# mLRS-tx-dualE28-top-v042.net
KiCad netlist of a schematic drawn in EAGLE
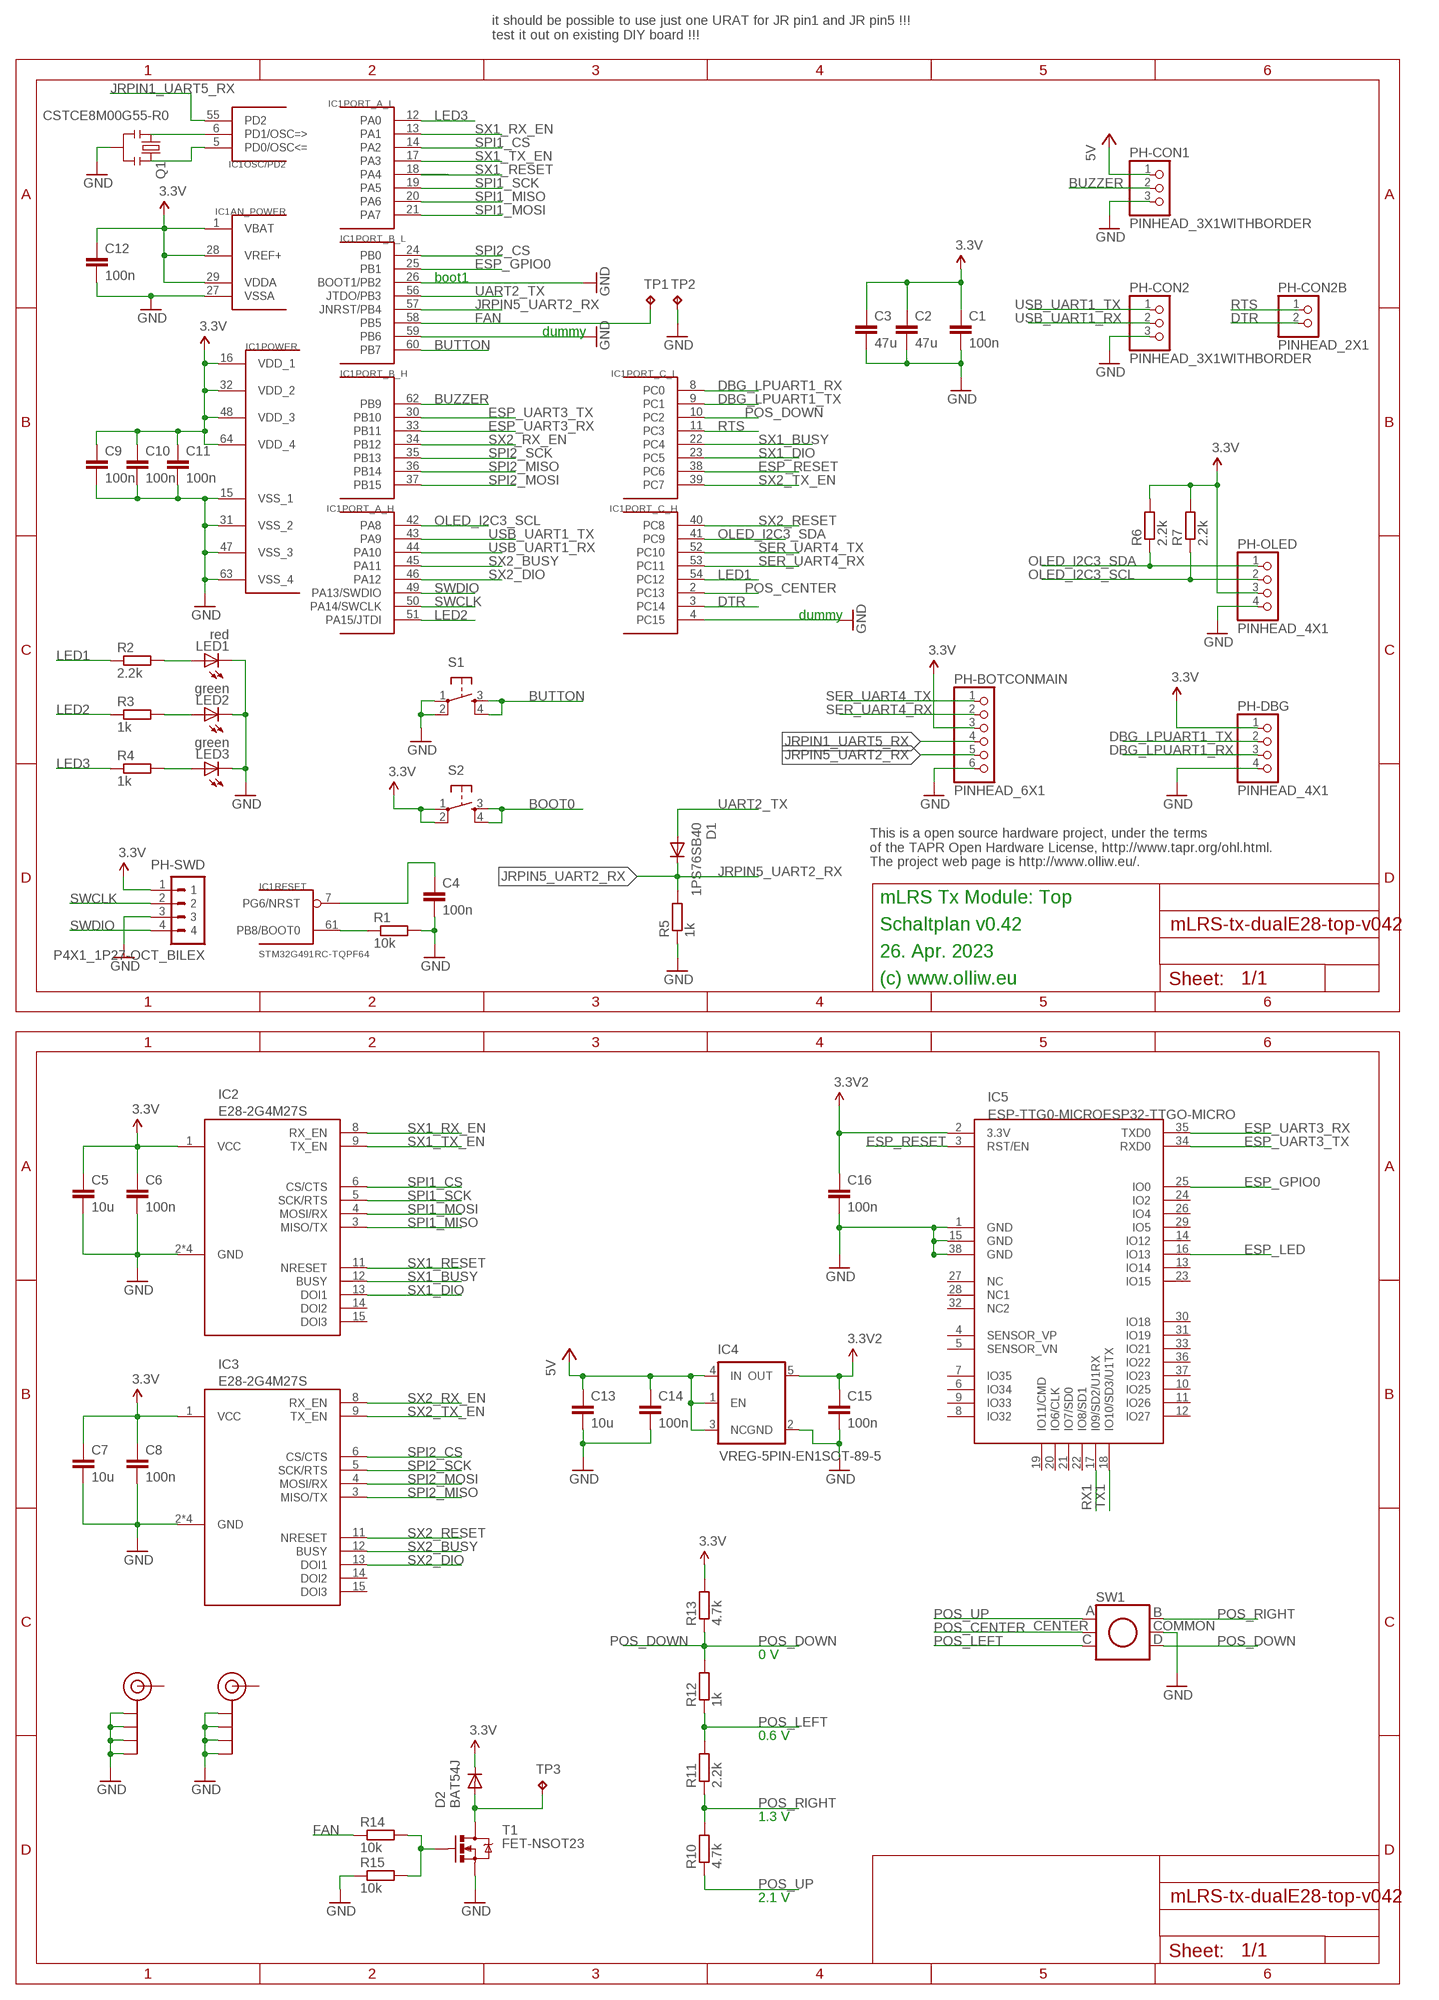
[diagram p0: schematic, sheet 1]

(export (version "E")
  (design (tool "Eeschema 10.0.6"))
  (components
    (comp (ref "C1")
      (value "100n")
      (footprint "eagle-import:C0402")
      (libsource (lib "eagle-import") (part "C-EUC0402"))
    )
    (comp (ref "C2")
      (value "47u")
      (footprint "eagle-import:C1210")
      (libsource (lib "eagle-import") (part "C-EUC1210"))
    )
    (comp (ref "C3")
      (value "47u")
      (footprint "eagle-import:C1206K")
      (libsource (lib "eagle-import") (part "C-EUC1206K"))
    )
    (comp (ref "C4")
      (value "100n")
      (footprint "eagle-import:C0402")
      (libsource (lib "eagle-import") (part "C-EUC0402"))
    )
    (comp (ref "C5")
      (value "10u")
      (footprint "eagle-import:C0603")
      (libsource (lib "eagle-import") (part "C-EUC0603"))
    )
    (comp (ref "C6")
      (value "100n")
      (footprint "eagle-import:C0402")
      (libsource (lib "eagle-import") (part "C-EUC0402"))
    )
    (comp (ref "C7")
      (value "10u")
      (footprint "eagle-import:C0603")
      (libsource (lib "eagle-import") (part "C-EUC0603"))
    )
    (comp (ref "C8")
      (value "100n")
      (footprint "eagle-import:C0402")
      (libsource (lib "eagle-import") (part "C-EUC0402"))
    )
    (comp (ref "C9")
      (value "100n")
      (footprint "eagle-import:C0402")
      (libsource (lib "eagle-import") (part "C-EUC0402"))
    )
    (comp (ref "C10")
      (value "100n")
      (footprint "eagle-import:C0402")
      (libsource (lib "eagle-import") (part "C-EUC0402"))
    )
    (comp (ref "C11")
      (value "100n")
      (footprint "eagle-import:C0402")
      (libsource (lib "eagle-import") (part "C-EUC0402"))
    )
    (comp (ref "C12")
      (value "100n")
      (footprint "eagle-import:C0402")
      (libsource (lib "eagle-import") (part "C-EUC0402"))
    )
    (comp (ref "C13")
      (value "10u")
      (footprint "eagle-import:C0603")
      (libsource (lib "eagle-import") (part "C-EUC0603"))
    )
    (comp (ref "C14")
      (value "100n")
      (footprint "eagle-import:C0402")
      (libsource (lib "eagle-import") (part "C-EUC0402"))
    )
    (comp (ref "C15")
      (value "100n")
      (footprint "eagle-import:C0402")
      (libsource (lib "eagle-import") (part "C-EUC0402"))
    )
    (comp (ref "C16")
      (value "100n")
      (footprint "eagle-import:C0603")
      (libsource (lib "eagle-import") (part "C-EUC0603"))
    )
    (comp (ref "D1")
      (value "1PS76SB40")
      (footprint "eagle-import:SOD110-R")
      (libsource (lib "eagle-import") (part "DIODE-SOD110-R"))
    )
    (comp (ref "D2")
      (value "BAT54J")
      (footprint "eagle-import:SOD110-R")
      (libsource (lib "eagle-import") (part "DIODE-SOD110-R"))
    )
    (comp (ref "IC1")
      (value "STM32G491RC-TQPF64")
      (footprint "eagle-import:TQFP64")
      (libsource (lib "eagle-import") (part "STM32G4X1RX-TQPF64"))
    )
    (comp (ref "IC2")
      (value "E28-2G4M27S")
      (footprint "eagle-import:E28-2G4M27")
      (libsource (lib "eagle-import") (part "E28"))
    )
    (comp (ref "IC3")
      (value "E28-2G4M27S")
      (footprint "eagle-import:E28-2G4M27")
      (libsource (lib "eagle-import") (part "E28"))
    )
    (comp (ref "IC4")
      (value "VREG-5PIN-EN1SOT-89-5")
      (footprint "eagle-import:SOT-89-5")
      (libsource (lib "eagle-import") (part "VREG-5PIN-EN1SOT-89-5"))
    )
    (comp (ref "IC5")
      (value "ESP-TTG0-MICROESP32-TTGO-MICRO")
      (footprint "eagle-import:ESP32-TTGO-MICRO")
      (libsource (lib "eagle-import") (part "ESP-TTG0-MICROESP32-TTGO-MICRO"))
    )
    (comp (ref "LED1")
      (value "red")
      (footprint "eagle-import:CHIPLED_0603")
      (libsource (lib "eagle-import") (part "LEDCHIPLED_0603"))
    )
    (comp (ref "LED2")
      (value "green")
      (footprint "eagle-import:CHIPLED_0603")
      (libsource (lib "eagle-import") (part "LEDCHIPLED_0603"))
    )
    (comp (ref "LED3")
      (value "green")
      (footprint "eagle-import:CHIPLED_0603")
      (libsource (lib "eagle-import") (part "LEDCHIPLED_0603"))
    )
    (comp (ref "PH-BOTCONMAIN")
      (value "PINHEAD_6X1")
      (footprint "eagle-import:PINHEAD_6X1")
      (libsource (lib "eagle-import") (part "PINHEAD_6X1"))
    )
    (comp (ref "PH-CON1")
      (value "PINHEAD_3X1WITHBORDER")
      (footprint "eagle-import:PINHEAD_3X1")
      (libsource (lib "eagle-import") (part "PINHEAD_3X1WITHBORDER"))
    )
    (comp (ref "PH-CON2")
      (value "PINHEAD_3X1WITHBORDER")
      (footprint "eagle-import:PINHEAD_3X1")
      (libsource (lib "eagle-import") (part "PINHEAD_3X1WITHBORDER"))
    )
    (comp (ref "PH-CON2B")
      (value "PINHEAD_2X1")
      (footprint "eagle-import:PINHEAD_2X1")
      (libsource (lib "eagle-import") (part "PINHEAD_2X1"))
    )
    (comp (ref "PH-DBG")
      (value "PINHEAD_4X1")
      (footprint "eagle-import:PINHEAD_4X1")
      (libsource (lib "eagle-import") (part "PINHEAD_4X1"))
    )
    (comp (ref "PH-OLED")
      (value "PINHEAD_4X1")
      (footprint "eagle-import:PINHEAD_4X1")
      (libsource (lib "eagle-import") (part "PINHEAD_4X1"))
    )
    (comp (ref "PH-SWD")
      (value "P4X1_1P27-OCT_BILEX")
      (footprint "eagle-import:4X1_1P27_OCT_BILEX")
      (libsource (lib "eagle-import") (part "P4X1_1P27-OCT_BILEX"))
    )
    (comp (ref "Q1")
      (value "CSTCE8M00G55-R0")
      (footprint "eagle-import:RESONATOR-SMD")
      (libsource (lib "eagle-import") (part "RESONATORSMD"))
    )
    (comp (ref "R1")
      (value "10k")
      (footprint "eagle-import:R0402")
      (libsource (lib "eagle-import") (part "R-EU_R0402"))
    )
    (comp (ref "R2")
      (value "2.2k")
      (footprint "eagle-import:R0402")
      (libsource (lib "eagle-import") (part "R-EU_R0402"))
    )
    (comp (ref "R3")
      (value "1k")
      (footprint "eagle-import:R0402")
      (libsource (lib "eagle-import") (part "R-EU_R0402"))
    )
    (comp (ref "R4")
      (value "1k")
      (footprint "eagle-import:R0402")
      (libsource (lib "eagle-import") (part "R-EU_R0402"))
    )
    (comp (ref "R5")
      (value "1k")
      (footprint "eagle-import:R0402")
      (libsource (lib "eagle-import") (part "R-EU_R0402"))
    )
    (comp (ref "R6")
      (value "2.2k")
      (footprint "eagle-import:R0402")
      (libsource (lib "eagle-import") (part "R-EU_R0402"))
    )
    (comp (ref "R7")
      (value "2.2k")
      (footprint "eagle-import:R0402")
      (libsource (lib "eagle-import") (part "R-EU_R0402"))
    )
    (comp (ref "R10")
      (value "4.7k")
      (footprint "eagle-import:R0402")
      (libsource (lib "eagle-import") (part "R-EU_R0402"))
    )
    (comp (ref "R11")
      (value "2.2k")
      (footprint "eagle-import:R0402")
      (libsource (lib "eagle-import") (part "R-EU_R0402"))
    )
    (comp (ref "R12")
      (value "1k")
      (footprint "eagle-import:R0402")
      (libsource (lib "eagle-import") (part "R-EU_R0402"))
    )
    (comp (ref "R13")
      (value "4.7k")
      (footprint "eagle-import:R0402")
      (libsource (lib "eagle-import") (part "R-EU_R0402"))
    )
    (comp (ref "R14")
      (value "10k")
      (footprint "eagle-import:R0402")
      (libsource (lib "eagle-import") (part "R-EU_R0402"))
    )
    (comp (ref "R15")
      (value "10k")
      (footprint "eagle-import:R0402")
      (libsource (lib "eagle-import") (part "R-EU_R0402"))
    )
    (comp (ref "RF1")
      (value "SMA_EDGE")
      (footprint "eagle-import:SMA-EDGE")
      (libsource (lib "eagle-import") (part "SMA_EDGE"))
    )
    (comp (ref "RF2")
      (value "SMA_EDGE")
      (footprint "eagle-import:SMA-EDGE")
      (libsource (lib "eagle-import") (part "SMA_EDGE"))
    )
    (comp (ref "S1")
      (value "TAC_SWITCHPTH")
      (footprint "eagle-import:TACTILE-PTH")
      (libsource (lib "eagle-import") (part "TAC_SWITCHPTH"))
    )
    (comp (ref "S2")
      (value "TAC_SWITCHPTH")
      (footprint "eagle-import:TACTILE-PTH")
      (libsource (lib "eagle-import") (part "TAC_SWITCHPTH"))
    )
    (comp (ref "SW1")
      (value "JOYSTICK-5WAY")
      (footprint "eagle-import:JOYSTICK-5WAY")
      (libsource (lib "eagle-import") (part "JOYSTICK-5WAY"))
    )
    (comp (ref "T1")
      (value "FET-NSOT23")
      (footprint "eagle-import:SOT23")
      (libsource (lib "eagle-import") (part "FET-NSOT23"))
    )
    (comp (ref "TP1")
      (value "TPB1,27")
      (footprint "eagle-import:B1,27")
      (libsource (lib "eagle-import") (part "TPB1,27"))
    )
    (comp (ref "TP2")
      (value "TPB1,27")
      (footprint "eagle-import:B1,27")
      (libsource (lib "eagle-import") (part "TPB1,27"))
    )
    (comp (ref "TP3")
      (value "TPB1,27")
      (footprint "eagle-import:B1,27")
      (libsource (lib "eagle-import") (part "TPB1,27"))
    )
  )
  (nets
    (net (code "1") (name "/BOOT0") (class "Default")
      (node (ref "IC1") (pin "61") (pinfunction "PB8/BOOT0_61") (pintype "input"))
      (node (ref "R1") (pin "1") (pinfunction "1_1") (pintype "passive"))
      (node (ref "S2") (pin "3") (pinfunction "3_3") (pintype "passive"))
      (node (ref "S2") (pin "4") (pinfunction "4_4") (pintype "passive"))
    )
    (net (code "2") (name "/BUTTON") (class "Default")
      (node (ref "IC1") (pin "60") (pinfunction "PB7_60") (pintype "bidirectional"))
      (node (ref "S1") (pin "3") (pinfunction "3_3") (pintype "passive"))
      (node (ref "S1") (pin "4") (pinfunction "4_4") (pintype "passive"))
    )
    (net (code "3") (name "/BUZZER") (class "Default")
      (node (ref "IC1") (pin "62") (pinfunction "PB9_62") (pintype "bidirectional"))
      (node (ref "PH-CON1") (pin "2") (pinfunction "3_2") (pintype "passive"))
    )
    (net (code "4") (name "/DBG_LPUART1_RX") (class "Default")
      (node (ref "IC1") (pin "8") (pinfunction "PC0_8") (pintype "bidirectional"))
      (node (ref "PH-DBG") (pin "3") (pinfunction "3_3") (pintype "passive"))
    )
    (net (code "5") (name "/DBG_LPUART1_TX") (class "Default")
      (node (ref "IC1") (pin "9") (pinfunction "PC1_9") (pintype "bidirectional"))
      (node (ref "PH-DBG") (pin "2") (pinfunction "2_2") (pintype "passive"))
    )
    (net (code "6") (name "/DTR") (class "Default")
      (node (ref "IC1") (pin "3") (pinfunction "PC14_3") (pintype "bidirectional"))
      (node (ref "PH-CON2B") (pin "2") (pinfunction "2_2") (pintype "passive"))
    )
    (net (code "7") (name "/ESP_GPIO0") (class "Default")
      (node (ref "IC1") (pin "25") (pinfunction "PB1_25") (pintype "bidirectional"))
      (node (ref "IC5") (pin "25") (pinfunction "IO0_25") (pintype "bidirectional"))
    )
    (net (code "8") (name "/ESP_LED") (class "Default")
      (node (ref "IC5") (pin "16") (pinfunction "IO13_16") (pintype "bidirectional"))
    )
    (net (code "9") (name "/ESP_RESET") (class "Default")
      (node (ref "IC1") (pin "38") (pinfunction "PC6_38") (pintype "bidirectional"))
      (node (ref "IC5") (pin "3") (pinfunction "RST/EN_3") (pintype "input"))
    )
    (net (code "10") (name "/ESP_UART3_RX") (class "Default")
      (node (ref "IC1") (pin "33") (pinfunction "PB11_33") (pintype "bidirectional"))
      (node (ref "IC5") (pin "35") (pinfunction "TXD0_35") (pintype "bidirectional"))
    )
    (net (code "11") (name "/ESP_UART3_TX") (class "Default")
      (node (ref "IC1") (pin "30") (pinfunction "PB10_30") (pintype "bidirectional"))
      (node (ref "IC5") (pin "34") (pinfunction "RXD0_34") (pintype "bidirectional"))
    )
    (net (code "12") (name "/FAN") (class "Default")
      (node (ref "IC1") (pin "58") (pinfunction "PB5_58") (pintype "bidirectional"))
      (node (ref "R14") (pin "1") (pinfunction "1_1") (pintype "passive"))
      (node (ref "TP1") (pin "TP") (pinfunction "TP_TP") (pintype "input"))
    )
    (net (code "13") (name "/LED1") (class "Default")
      (node (ref "IC1") (pin "54") (pinfunction "PC12_54") (pintype "bidirectional"))
      (node (ref "R2") (pin "1") (pinfunction "1_1") (pintype "passive"))
    )
    (net (code "14") (name "/LED2") (class "Default")
      (node (ref "IC1") (pin "51") (pinfunction "PA15/JTDI_51") (pintype "bidirectional"))
      (node (ref "R3") (pin "1") (pinfunction "1_1") (pintype "passive"))
    )
    (net (code "15") (name "/LED3") (class "Default")
      (node (ref "IC1") (pin "12") (pinfunction "PA0_12") (pintype "bidirectional"))
      (node (ref "R4") (pin "1") (pinfunction "1_1") (pintype "passive"))
    )
    (net (code "16") (name "/OLED_I2C3_SCL") (class "Default")
      (node (ref "IC1") (pin "42") (pinfunction "PA8_42") (pintype "bidirectional"))
      (node (ref "PH-OLED") (pin "2") (pinfunction "2_2") (pintype "passive"))
      (node (ref "R7") (pin "1") (pinfunction "1_1") (pintype "passive"))
    )
    (net (code "17") (name "/OLED_I2C3_SDA") (class "Default")
      (node (ref "IC1") (pin "41") (pinfunction "PC9_41") (pintype "bidirectional"))
      (node (ref "PH-OLED") (pin "1") (pinfunction "1_1") (pintype "passive"))
      (node (ref "R6") (pin "1") (pinfunction "1_1") (pintype "passive"))
    )
    (net (code "18") (name "/POS_CENTER") (class "Default")
      (node (ref "IC1") (pin "2") (pinfunction "PC13_2") (pintype "bidirectional"))
      (node (ref "SW1") (pin "2") (pinfunction "CENTER_2") (pintype "bidirectional"))
    )
    (net (code "19") (name "/POS_DOWN") (class "Default")
      (node (ref "IC1") (pin "10") (pinfunction "PC2_10") (pintype "bidirectional"))
      (node (ref "R12") (pin "2") (pinfunction "2_2") (pintype "passive"))
      (node (ref "R13") (pin "1") (pinfunction "1_1") (pintype "passive"))
      (node (ref "SW1") (pin "6") (pinfunction "D_6") (pintype "bidirectional"))
    )
    (net (code "20") (name "/POS_LEFT") (class "Default")
      (node (ref "R11") (pin "2") (pinfunction "2_2") (pintype "passive"))
      (node (ref "R12") (pin "1") (pinfunction "1_1") (pintype "passive"))
      (node (ref "SW1") (pin "3") (pinfunction "C_3") (pintype "bidirectional"))
    )
    (net (code "21") (name "/POS_RIGHT") (class "Default")
      (node (ref "R10") (pin "2") (pinfunction "2_2") (pintype "passive"))
      (node (ref "R11") (pin "1") (pinfunction "1_1") (pintype "passive"))
      (node (ref "SW1") (pin "4") (pinfunction "B_4") (pintype "bidirectional"))
    )
    (net (code "22") (name "/POS_UP") (class "Default")
      (node (ref "R10") (pin "1") (pinfunction "1_1") (pintype "passive"))
      (node (ref "SW1") (pin "1") (pinfunction "A_1") (pintype "bidirectional"))
    )
    (net (code "23") (name "/RTS") (class "Default")
      (node (ref "IC1") (pin "11") (pinfunction "PC3_11") (pintype "bidirectional"))
      (node (ref "PH-CON2B") (pin "1") (pinfunction "1_1") (pintype "passive"))
    )
    (net (code "24") (name "/RX1") (class "Default")
      (node (ref "IC5") (pin "17") (pinfunction "I09/SD2/U1RX_17") (pintype "bidirectional"))
    )
    (net (code "25") (name "/SER_UART4_RX") (class "Default")
      (node (ref "IC1") (pin "53") (pinfunction "PC11_53") (pintype "bidirectional"))
      (node (ref "PH-BOTCONMAIN") (pin "2") (pinfunction "2_2") (pintype "passive"))
    )
    (net (code "26") (name "/SER_UART4_TX") (class "Default")
      (node (ref "IC1") (pin "52") (pinfunction "PC10_52") (pintype "bidirectional"))
      (node (ref "PH-BOTCONMAIN") (pin "1") (pinfunction "1_1") (pintype "passive"))
    )
    (net (code "27") (name "/SPI1_CS") (class "Default")
      (node (ref "IC1") (pin "14") (pinfunction "PA2_14") (pintype "bidirectional"))
      (node (ref "IC2") (pin "6") (pinfunction "CS/CTS_6") (pintype "bidirectional"))
    )
    (net (code "28") (name "/SPI1_MISO") (class "Default")
      (node (ref "IC1") (pin "20") (pinfunction "PA6_20") (pintype "bidirectional"))
      (node (ref "IC2") (pin "3") (pinfunction "MISO/TX_3") (pintype "bidirectional"))
    )
    (net (code "29") (name "/SPI1_MOSI") (class "Default")
      (node (ref "IC1") (pin "21") (pinfunction "PA7_21") (pintype "bidirectional"))
      (node (ref "IC2") (pin "4") (pinfunction "MOSI/RX_4") (pintype "bidirectional"))
    )
    (net (code "30") (name "/SPI1_SCK") (class "Default")
      (node (ref "IC1") (pin "19") (pinfunction "PA5_19") (pintype "bidirectional"))
      (node (ref "IC2") (pin "5") (pinfunction "SCK/RTS_5") (pintype "bidirectional"))
    )
    (net (code "31") (name "/SPI2_CS") (class "Default")
      (node (ref "IC1") (pin "24") (pinfunction "PB0_24") (pintype "bidirectional"))
      (node (ref "IC3") (pin "6") (pinfunction "CS/CTS_6") (pintype "bidirectional"))
    )
    (net (code "32") (name "/SPI2_MISO") (class "Default")
      (node (ref "IC1") (pin "36") (pinfunction "PB14_36") (pintype "bidirectional"))
      (node (ref "IC3") (pin "3") (pinfunction "MISO/TX_3") (pintype "bidirectional"))
    )
    (net (code "33") (name "/SPI2_MOSI") (class "Default")
      (node (ref "IC1") (pin "37") (pinfunction "PB15_37") (pintype "bidirectional"))
      (node (ref "IC3") (pin "4") (pinfunction "MOSI/RX_4") (pintype "bidirectional"))
    )
    (net (code "34") (name "/SPI2_SCK") (class "Default")
      (node (ref "IC1") (pin "35") (pinfunction "PB13_35") (pintype "bidirectional"))
      (node (ref "IC3") (pin "5") (pinfunction "SCK/RTS_5") (pintype "bidirectional"))
    )
    (net (code "35") (name "/SWCLK") (class "Default")
      (node (ref "IC1") (pin "50") (pinfunction "PA14/SWCLK_50") (pintype "bidirectional"))
      (node (ref "PH-SWD") (pin "2") (pinfunction "2_2") (pintype "passive"))
    )
    (net (code "36") (name "/SWDIO") (class "Default")
      (node (ref "IC1") (pin "49") (pinfunction "PA13/SWDIO_49") (pintype "bidirectional"))
      (node (ref "PH-SWD") (pin "4") (pinfunction "4_4") (pintype "passive"))
    )
    (net (code "37") (name "/SX1_BUSY") (class "Default")
      (node (ref "IC1") (pin "22") (pinfunction "PC4_22") (pintype "bidirectional"))
      (node (ref "IC2") (pin "12") (pinfunction "BUSY_12") (pintype "bidirectional"))
    )
    (net (code "38") (name "/SX1_DIO") (class "Default")
      (node (ref "IC1") (pin "23") (pinfunction "PC5_23") (pintype "bidirectional"))
      (node (ref "IC2") (pin "13") (pinfunction "DOI1_13") (pintype "bidirectional"))
    )
    (net (code "39") (name "/SX1_RESET") (class "Default")
      (node (ref "IC1") (pin "18") (pinfunction "PA4_18") (pintype "bidirectional"))
      (node (ref "IC2") (pin "11") (pinfunction "NRESET_11") (pintype "input"))
    )
    (net (code "40") (name "/SX1_RX_EN") (class "Default")
      (node (ref "IC1") (pin "13") (pinfunction "PA1_13") (pintype "bidirectional"))
      (node (ref "IC2") (pin "8") (pinfunction "RX_EN_8") (pintype "bidirectional"))
    )
    (net (code "41") (name "/SX1_TX_EN") (class "Default")
      (node (ref "IC1") (pin "17") (pinfunction "PA3_17") (pintype "bidirectional"))
      (node (ref "IC2") (pin "9") (pinfunction "TX_EN_9") (pintype "bidirectional"))
    )
    (net (code "42") (name "/SX2_BUSY") (class "Default")
      (node (ref "IC1") (pin "45") (pinfunction "PA11_45") (pintype "bidirectional"))
      (node (ref "IC3") (pin "12") (pinfunction "BUSY_12") (pintype "bidirectional"))
    )
    (net (code "43") (name "/SX2_DIO") (class "Default")
      (node (ref "IC1") (pin "46") (pinfunction "PA12_46") (pintype "bidirectional"))
      (node (ref "IC3") (pin "13") (pinfunction "DOI1_13") (pintype "bidirectional"))
    )
    (net (code "44") (name "/SX2_RESET") (class "Default")
      (node (ref "IC1") (pin "40") (pinfunction "PC8_40") (pintype "bidirectional"))
      (node (ref "IC3") (pin "11") (pinfunction "NRESET_11") (pintype "input"))
    )
    (net (code "45") (name "/SX2_RX_EN") (class "Default")
      (node (ref "IC1") (pin "34") (pinfunction "PB12_34") (pintype "bidirectional"))
      (node (ref "IC3") (pin "8") (pinfunction "RX_EN_8") (pintype "bidirectional"))
    )
    (net (code "46") (name "/SX2_TX_EN") (class "Default")
      (node (ref "IC1") (pin "39") (pinfunction "PC7_39") (pintype "bidirectional"))
      (node (ref "IC3") (pin "9") (pinfunction "TX_EN_9") (pintype "bidirectional"))
    )
    (net (code "47") (name "/TX1") (class "Default")
      (node (ref "IC5") (pin "18") (pinfunction "IO10/SD3/U1TX_18") (pintype "bidirectional"))
    )
    (net (code "48") (name "/UART2_TX") (class "Default")
      (node (ref "D1") (pin "A") (pinfunction "A_A") (pintype "passive"))
      (node (ref "IC1") (pin "56") (pinfunction "JTDO/PB3_56") (pintype "bidirectional"))
    )
    (net (code "49") (name "/USB_UART1_RX") (class "Default")
      (node (ref "IC1") (pin "44") (pinfunction "PA10_44") (pintype "bidirectional"))
      (node (ref "PH-CON2") (pin "2") (pinfunction "3_2") (pintype "passive"))
    )
    (net (code "50") (name "/USB_UART1_TX") (class "Default")
      (node (ref "IC1") (pin "43") (pinfunction "PA9_43") (pintype "bidirectional"))
      (node (ref "PH-CON2") (pin "1") (pinfunction "1_1") (pintype "passive"))
    )
    (net (code "51") (name "3.3V") (class "Default")
      (node (ref "C1") (pin "1") (pinfunction "1_1") (pintype "passive"))
      (node (ref "C10") (pin "1") (pinfunction "1_1") (pintype "passive"))
      (node (ref "C11") (pin "1") (pinfunction "1_1") (pintype "passive"))
      (node (ref "C12") (pin "1") (pinfunction "1_1") (pintype "passive"))
      (node (ref "C2") (pin "1") (pinfunction "1_1") (pintype "passive"))
      (node (ref "C3") (pin "1") (pinfunction "1_1") (pintype "passive"))
      (node (ref "C5") (pin "1") (pinfunction "1_1") (pintype "passive"))
      (node (ref "C6") (pin "1") (pinfunction "1_1") (pintype "passive"))
      (node (ref "C7") (pin "1") (pinfunction "1_1") (pintype "passive"))
      (node (ref "C8") (pin "1") (pinfunction "1_1") (pintype "passive"))
      (node (ref "C9") (pin "1") (pinfunction "1_1") (pintype "passive"))
      (node (ref "D2") (pin "C") (pinfunction "C_C") (pintype "passive"))
      (node (ref "IC1") (pin "1") (pinfunction "VBAT_1") (pintype "power_in"))
      (node (ref "IC1") (pin "16") (pinfunction "VDD_1_16") (pintype "power_in"))
      (node (ref "IC1") (pin "28") (pinfunction "VREF+_28") (pintype "input"))
      (node (ref "IC1") (pin "29") (pinfunction "VDDA_29") (pintype "power_in"))
      (node (ref "IC1") (pin "32") (pinfunction "VDD_2_32") (pintype "power_in"))
      (node (ref "IC1") (pin "48") (pinfunction "VDD_3_48") (pintype "power_in"))
      (node (ref "IC1") (pin "64") (pinfunction "VDD_4_64") (pintype "power_in"))
      (node (ref "IC2") (pin "1") (pinfunction "VCC_1") (pintype "power_in"))
      (node (ref "IC3") (pin "1") (pinfunction "VCC_1") (pintype "power_in"))
      (node (ref "PH-BOTCONMAIN") (pin "3") (pinfunction "3_3") (pintype "passive"))
      (node (ref "PH-DBG") (pin "1") (pinfunction "1_1") (pintype "passive"))
      (node (ref "PH-OLED") (pin "3") (pinfunction "3_3") (pintype "passive"))
      (node (ref "PH-SWD") (pin "1") (pinfunction "1_1") (pintype "passive"))
      (node (ref "R13") (pin "2") (pinfunction "2_2") (pintype "passive"))
      (node (ref "R6") (pin "2") (pinfunction "2_2") (pintype "passive"))
      (node (ref "R7") (pin "2") (pinfunction "2_2") (pintype "passive"))
      (node (ref "S2") (pin "1") (pinfunction "1_1") (pintype "passive"))
      (node (ref "S2") (pin "2") (pinfunction "2_2") (pintype "passive"))
    )
    (net (code "52") (name "3.3V2") (class "Default")
      (node (ref "C15") (pin "1") (pinfunction "1_1") (pintype "passive"))
      (node (ref "C16") (pin "1") (pinfunction "1_1") (pintype "passive"))
      (node (ref "IC4") (pin "5") (pinfunction "OUT_5") (pintype "output"))
      (node (ref "IC5") (pin "2") (pinfunction "3.3V_2") (pintype "power_in"))
    )
    (net (code "53") (name "5V") (class "Default")
      (node (ref "C13") (pin "1") (pinfunction "1_1") (pintype "passive"))
      (node (ref "C14") (pin "1") (pinfunction "1_1") (pintype "passive"))
      (node (ref "IC4") (pin "1") (pinfunction "EN_1") (pintype "input"))
      (node (ref "IC4") (pin "3") (pinfunction "NC_3") (pintype "passive"))
      (node (ref "IC4") (pin "4") (pinfunction "IN_4") (pintype "power_in"))
      (node (ref "PH-CON1") (pin "1") (pinfunction "1_1") (pintype "passive"))
    )
    (net (code "54") (name "GND") (class "Default")
      (node (ref "C1") (pin "2") (pinfunction "2_2") (pintype "passive"))
      (node (ref "C10") (pin "2") (pinfunction "2_2") (pintype "passive"))
      (node (ref "C11") (pin "2") (pinfunction "2_2") (pintype "passive"))
      (node (ref "C12") (pin "2") (pinfunction "2_2") (pintype "passive"))
      (node (ref "C13") (pin "2") (pinfunction "2_2") (pintype "passive"))
      (node (ref "C14") (pin "2") (pinfunction "2_2") (pintype "passive"))
      (node (ref "C15") (pin "2") (pinfunction "2_2") (pintype "passive"))
      (node (ref "C16") (pin "2") (pinfunction "2_2") (pintype "passive"))
      (node (ref "C2") (pin "2") (pinfunction "2_2") (pintype "passive"))
      (node (ref "C3") (pin "2") (pinfunction "2_2") (pintype "passive"))
      (node (ref "C4") (pin "2") (pinfunction "2_2") (pintype "passive"))
      (node (ref "C5") (pin "2") (pinfunction "2_2") (pintype "passive"))
      (node (ref "C6") (pin "2") (pinfunction "2_2") (pintype "passive"))
      (node (ref "C7") (pin "2") (pinfunction "2_2") (pintype "passive"))
      (node (ref "C8") (pin "2") (pinfunction "2_2") (pintype "passive"))
      (node (ref "C9") (pin "2") (pinfunction "2_2") (pintype "passive"))
      (node (ref "IC1") (pin "15") (pinfunction "VSS_1_15") (pintype "power_in"))
      (node (ref "IC1") (pin "26") (pinfunction "BOOT1/PB2_26") (pintype "bidirectional"))
      (node (ref "IC1") (pin "27") (pinfunction "VSSA_27") (pintype "power_in"))
      (node (ref "IC1") (pin "31") (pinfunction "VSS_2_31") (pintype "power_in"))
      (node (ref "IC1") (pin "4") (pinfunction "PC15_4") (pintype "bidirectional"))
      (node (ref "IC1") (pin "47") (pinfunction "VSS_3_47") (pintype "power_in"))
      (node (ref "IC1") (pin "59") (pinfunction "PB6_59") (pintype "bidirectional"))
      (node (ref "IC1") (pin "63") (pinfunction "VSS_4_63") (pintype "power_in"))
      (node (ref "IC2") (pin "10") (pinfunction "GND_10") (pintype "power_in"))
      (node (ref "IC2") (pin "16") (pinfunction "GND_16") (pintype "power_in"))
      (node (ref "IC2") (pin "2") (pinfunction "GND_2") (pintype "power_in"))
      (node (ref "IC2") (pin "7") (pinfunction "GND_7") (pintype "power_in"))
      (node (ref "IC3") (pin "10") (pinfunction "GND_10") (pintype "power_in"))
      (node (ref "IC3") (pin "16") (pinfunction "GND_16") (pintype "power_in"))
      (node (ref "IC3") (pin "2") (pinfunction "GND_2") (pintype "power_in"))
      (node (ref "IC3") (pin "7") (pinfunction "GND_7") (pintype "power_in"))
      (node (ref "IC4") (pin "2") (pinfunction "GND_2") (pintype "power_in"))
      (node (ref "IC5") (pin "1") (pinfunction "GND_1") (pintype "power_in"))
      (node (ref "IC5") (pin "15") (pinfunction "GND_15") (pintype "power_in"))
      (node (ref "IC5") (pin "38") (pinfunction "GND_38") (pintype "power_in"))
      (node (ref "LED1") (pin "C") (pinfunction "C_C") (pintype "passive"))
      (node (ref "LED2") (pin "C") (pinfunction "C_C") (pintype "passive"))
      (node (ref "LED3") (pin "C") (pinfunction "C_C") (pintype "passive"))
      (node (ref "PH-BOTCONMAIN") (pin "6") (pinfunction "6_6") (pintype "passive"))
      (node (ref "PH-CON1") (pin "3") (pinfunction "5_3") (pintype "passive"))
      (node (ref "PH-CON2") (pin "3") (pinfunction "5_3") (pintype "passive"))
      (node (ref "PH-DBG") (pin "4") (pinfunction "4_4") (pintype "passive"))
      (node (ref "PH-OLED") (pin "4") (pinfunction "4_4") (pintype "passive"))
      (node (ref "PH-SWD") (pin "3") (pinfunction "3_3") (pintype "passive"))
      (node (ref "Q1") (pin "2") (pinfunction "2_2") (pintype "passive"))
      (node (ref "R1") (pin "2") (pinfunction "2_2") (pintype "passive"))
      (node (ref "R15") (pin "1") (pinfunction "1_1") (pintype "passive"))
      (node (ref "R5") (pin "1") (pinfunction "1_1") (pintype "passive"))
      (node (ref "RF1") (pin "GND@0") (pinfunction "GND_GND@0") (pintype "bidirectional"))
      (node (ref "RF1") (pin "GND@1") (pinfunction "GND_GND@1") (pintype "bidirectional"))
      (node (ref "RF1") (pin "GND@2") (pinfunction "GND_GND@2") (pintype "bidirectional"))
      (node (ref "RF1") (pin "GND@3") (pinfunction "GND_GND@3") (pintype "bidirectional"))
      (node (ref "RF2") (pin "GND@0") (pinfunction "GND_GND@0") (pintype "bidirectional"))
      (node (ref "RF2") (pin "GND@1") (pinfunction "GND_GND@1") (pintype "bidirectional"))
      (node (ref "RF2") (pin "GND@2") (pinfunction "GND_GND@2") (pintype "bidirectional"))
      (node (ref "RF2") (pin "GND@3") (pinfunction "GND_GND@3") (pintype "bidirectional"))
      (node (ref "S1") (pin "1") (pinfunction "1_1") (pintype "passive"))
      (node (ref "S1") (pin "2") (pinfunction "2_2") (pintype "passive"))
      (node (ref "SW1") (pin "5") (pinfunction "COMMON_5") (pintype "bidirectional"))
      (node (ref "T1") (pin "2") (pinfunction "S_2") (pintype "passive"))
      (node (ref "TP2") (pin "TP") (pinfunction "TP_TP") (pintype "input"))
    )
    (net (code "55") (name "JRPIN1_UART5_RX") (class "Default")
      (node (ref "IC1") (pin "55") (pinfunction "PD2_55") (pintype "bidirectional"))
      (node (ref "PH-BOTCONMAIN") (pin "4") (pinfunction "4_4") (pintype "passive"))
    )
    (net (code "56") (name "JRPIN5_UART2_RX") (class "Default")
      (node (ref "D1") (pin "C") (pinfunction "C_C") (pintype "passive"))
      (node (ref "IC1") (pin "57") (pinfunction "JNRST/PB4_57") (pintype "bidirectional"))
      (node (ref "PH-BOTCONMAIN") (pin "5") (pinfunction "5_5") (pintype "passive"))
      (node (ref "R5") (pin "2") (pinfunction "2_2") (pintype "passive"))
    )
    (net (code "57") (name "Net-(IC1B-PD0{slash}OSC<=)") (class "Default")
      (node (ref "IC1") (pin "5") (pinfunction "PD0/OSC<=_5") (pintype "bidirectional"))
      (node (ref "Q1") (pin "3") (pinfunction "3_3") (pintype "passive"))
    )
    (net (code "58") (name "Net-(IC1B-PD1{slash}OSC=>)") (class "Default")
      (node (ref "IC1") (pin "6") (pinfunction "PD1/OSC=>_6") (pintype "bidirectional"))
      (node (ref "Q1") (pin "1") (pinfunction "1_1") (pintype "passive"))
    )
    (net (code "59") (name "Net-(IC1J-PG6{slash}NRST)") (class "Default")
      (node (ref "C4") (pin "1") (pinfunction "1_1") (pintype "passive"))
      (node (ref "IC1") (pin "7") (pinfunction "PG6/NRST_7") (pintype "input"))
    )
    (net (code "60") (name "Net-(LED1-PadA)") (class "Default")
      (node (ref "LED1") (pin "A") (pinfunction "A_A") (pintype "passive"))
      (node (ref "R2") (pin "2") (pinfunction "2_2") (pintype "passive"))
    )
    (net (code "61") (name "Net-(LED2-PadA)") (class "Default")
      (node (ref "LED2") (pin "A") (pinfunction "A_A") (pintype "passive"))
      (node (ref "R3") (pin "2") (pinfunction "2_2") (pintype "passive"))
    )
    (net (code "62") (name "Net-(LED3-PadA)") (class "Default")
      (node (ref "LED3") (pin "A") (pinfunction "A_A") (pintype "passive"))
      (node (ref "R4") (pin "2") (pinfunction "2_2") (pintype "passive"))
    )
    (net (code "63") (name "Net-(T1-D)") (class "Default")
      (node (ref "D2") (pin "A") (pinfunction "A_A") (pintype "passive"))
      (node (ref "T1") (pin "3") (pinfunction "D_3") (pintype "passive"))
      (node (ref "TP3") (pin "TP") (pinfunction "TP_TP") (pintype "input"))
    )
    (net (code "64") (name "Net-(T1-G)") (class "Default")
      (node (ref "R14") (pin "2") (pinfunction "2_2") (pintype "passive"))
      (node (ref "R15") (pin "2") (pinfunction "2_2") (pintype "passive"))
      (node (ref "T1") (pin "1") (pinfunction "G_1") (pintype "passive"))
    )
    (net (code "65") (name "unconnected-(IC2-DOI2-Pad14)") (class "Default")
      (node (ref "IC2") (pin "14") (pinfunction "DOI2_14") (pintype "bidirectional"))
    )
    (net (code "66") (name "unconnected-(IC2-DOI3-Pad15)") (class "Default")
      (node (ref "IC2") (pin "15") (pinfunction "DOI3_15") (pintype "bidirectional"))
    )
    (net (code "67") (name "unconnected-(IC3-DOI2-Pad14)") (class "Default")
      (node (ref "IC3") (pin "14") (pinfunction "DOI2_14") (pintype "bidirectional"))
    )
    (net (code "68") (name "unconnected-(IC3-DOI3-Pad15)") (class "Default")
      (node (ref "IC3") (pin "15") (pinfunction "DOI3_15") (pintype "bidirectional"))
    )
    (net (code "69") (name "unconnected-(IC5-IO2-Pad24)") (class "Default")
      (node (ref "IC5") (pin "24") (pinfunction "IO2_24") (pintype "bidirectional"))
    )
    (net (code "70") (name "unconnected-(IC5-IO4-Pad26)") (class "Default")
      (node (ref "IC5") (pin "26") (pinfunction "IO4_26") (pintype "bidirectional"))
    )
    (net (code "71") (name "unconnected-(IC5-IO5-Pad29)") (class "Default")
      (node (ref "IC5") (pin "29") (pinfunction "IO5_29") (pintype "bidirectional"))
    )
    (net (code "72") (name "unconnected-(IC5-IO6{slash}CLK-Pad20)") (class "Default")
      (node (ref "IC5") (pin "20") (pinfunction "IO6/CLK_20") (pintype "bidirectional"))
    )
    (net (code "73") (name "unconnected-(IC5-IO7{slash}SD0-Pad21)") (class "Default")
      (node (ref "IC5") (pin "21") (pinfunction "IO7/SD0_21") (pintype "bidirectional"))
    )
    (net (code "74") (name "unconnected-(IC5-IO8{slash}SD1-Pad22)") (class "Default")
      (node (ref "IC5") (pin "22") (pinfunction "IO8/SD1_22") (pintype "bidirectional"))
    )
    (net (code "75") (name "unconnected-(IC5-IO11{slash}CMD-Pad19)") (class "Default")
      (node (ref "IC5") (pin "19") (pinfunction "IO11/CMD_19") (pintype "bidirectional"))
    )
    (net (code "76") (name "unconnected-(IC5-IO12-Pad14)") (class "Default")
      (node (ref "IC5") (pin "14") (pinfunction "IO12_14") (pintype "bidirectional"))
    )
    (net (code "77") (name "unconnected-(IC5-IO14-Pad13)") (class "Default")
      (node (ref "IC5") (pin "13") (pinfunction "IO14_13") (pintype "bidirectional"))
    )
    (net (code "78") (name "unconnected-(IC5-IO15-Pad23)") (class "Default")
      (node (ref "IC5") (pin "23") (pinfunction "IO15_23") (pintype "bidirectional"))
    )
    (net (code "79") (name "unconnected-(IC5-IO18-Pad30)") (class "Default")
      (node (ref "IC5") (pin "30") (pinfunction "IO18_30") (pintype "bidirectional"))
    )
    (net (code "80") (name "unconnected-(IC5-IO19-Pad31)") (class "Default")
      (node (ref "IC5") (pin "31") (pinfunction "IO19_31") (pintype "bidirectional"))
    )
    (net (code "81") (name "unconnected-(IC5-IO21-Pad33)") (class "Default")
      (node (ref "IC5") (pin "33") (pinfunction "IO21_33") (pintype "bidirectional"))
    )
    (net (code "82") (name "unconnected-(IC5-IO22-Pad36)") (class "Default")
      (node (ref "IC5") (pin "36") (pinfunction "IO22_36") (pintype "bidirectional"))
    )
    (net (code "83") (name "unconnected-(IC5-IO23-Pad37)") (class "Default")
      (node (ref "IC5") (pin "37") (pinfunction "IO23_37") (pintype "bidirectional"))
    )
    (net (code "84") (name "unconnected-(IC5-IO25-Pad10)") (class "Default")
      (node (ref "IC5") (pin "10") (pinfunction "IO25_10") (pintype "bidirectional"))
    )
    (net (code "85") (name "unconnected-(IC5-IO26-Pad11)") (class "Default")
      (node (ref "IC5") (pin "11") (pinfunction "IO26_11") (pintype "bidirectional"))
    )
    (net (code "86") (name "unconnected-(IC5-IO27-Pad12)") (class "Default")
      (node (ref "IC5") (pin "12") (pinfunction "IO27_12") (pintype "bidirectional"))
    )
    (net (code "87") (name "unconnected-(IC5-IO32-Pad8)") (class "Default")
      (node (ref "IC5") (pin "8") (pinfunction "IO32_8") (pintype "bidirectional"))
    )
    (net (code "88") (name "unconnected-(IC5-IO33-Pad9)") (class "Default")
      (node (ref "IC5") (pin "9") (pinfunction "IO33_9") (pintype "bidirectional"))
    )
    (net (code "89") (name "unconnected-(IC5-IO34-Pad6)") (class "Default")
      (node (ref "IC5") (pin "6") (pinfunction "IO34_6") (pintype "bidirectional"))
    )
    (net (code "90") (name "unconnected-(IC5-IO35-Pad7)") (class "Default")
      (node (ref "IC5") (pin "7") (pinfunction "IO35_7") (pintype "bidirectional"))
    )
    (net (code "91") (name "unconnected-(IC5-NC-Pad27)") (class "Default")
      (node (ref "IC5") (pin "27") (pinfunction "NC_27") (pintype "no_connect"))
    )
    (net (code "92") (name "unconnected-(IC5-NC1-Pad28)") (class "Default")
      (node (ref "IC5") (pin "28") (pinfunction "NC1_28") (pintype "no_connect"))
    )
    (net (code "93") (name "unconnected-(IC5-NC2-Pad32)") (class "Default")
      (node (ref "IC5") (pin "32") (pinfunction "NC2_32") (pintype "no_connect"))
    )
    (net (code "94") (name "unconnected-(IC5-SENSOR_VN-Pad5)") (class "Default")
      (node (ref "IC5") (pin "5") (pinfunction "SENSOR_VN_5") (pintype "bidirectional"))
    )
    (net (code "95") (name "unconnected-(IC5-SENSOR_VP-Pad4)") (class "Default")
      (node (ref "IC5") (pin "4") (pinfunction "SENSOR_VP_4") (pintype "bidirectional"))
    )
    (net (code "96") (name "unconnected-(RF1-SIGNAL-PadSIG)") (class "Default")
      (node (ref "RF1") (pin "SIG") (pinfunction "SIGNAL_SIG") (pintype "bidirectional"))
    )
    (net (code "97") (name "unconnected-(RF2-SIGNAL-PadSIG)") (class "Default")
      (node (ref "RF2") (pin "SIG") (pinfunction "SIGNAL_SIG") (pintype "bidirectional"))
    )
  )
)
